# BATT_INPUT.net
KiCad netlist of a schematic drawn in EAGLE
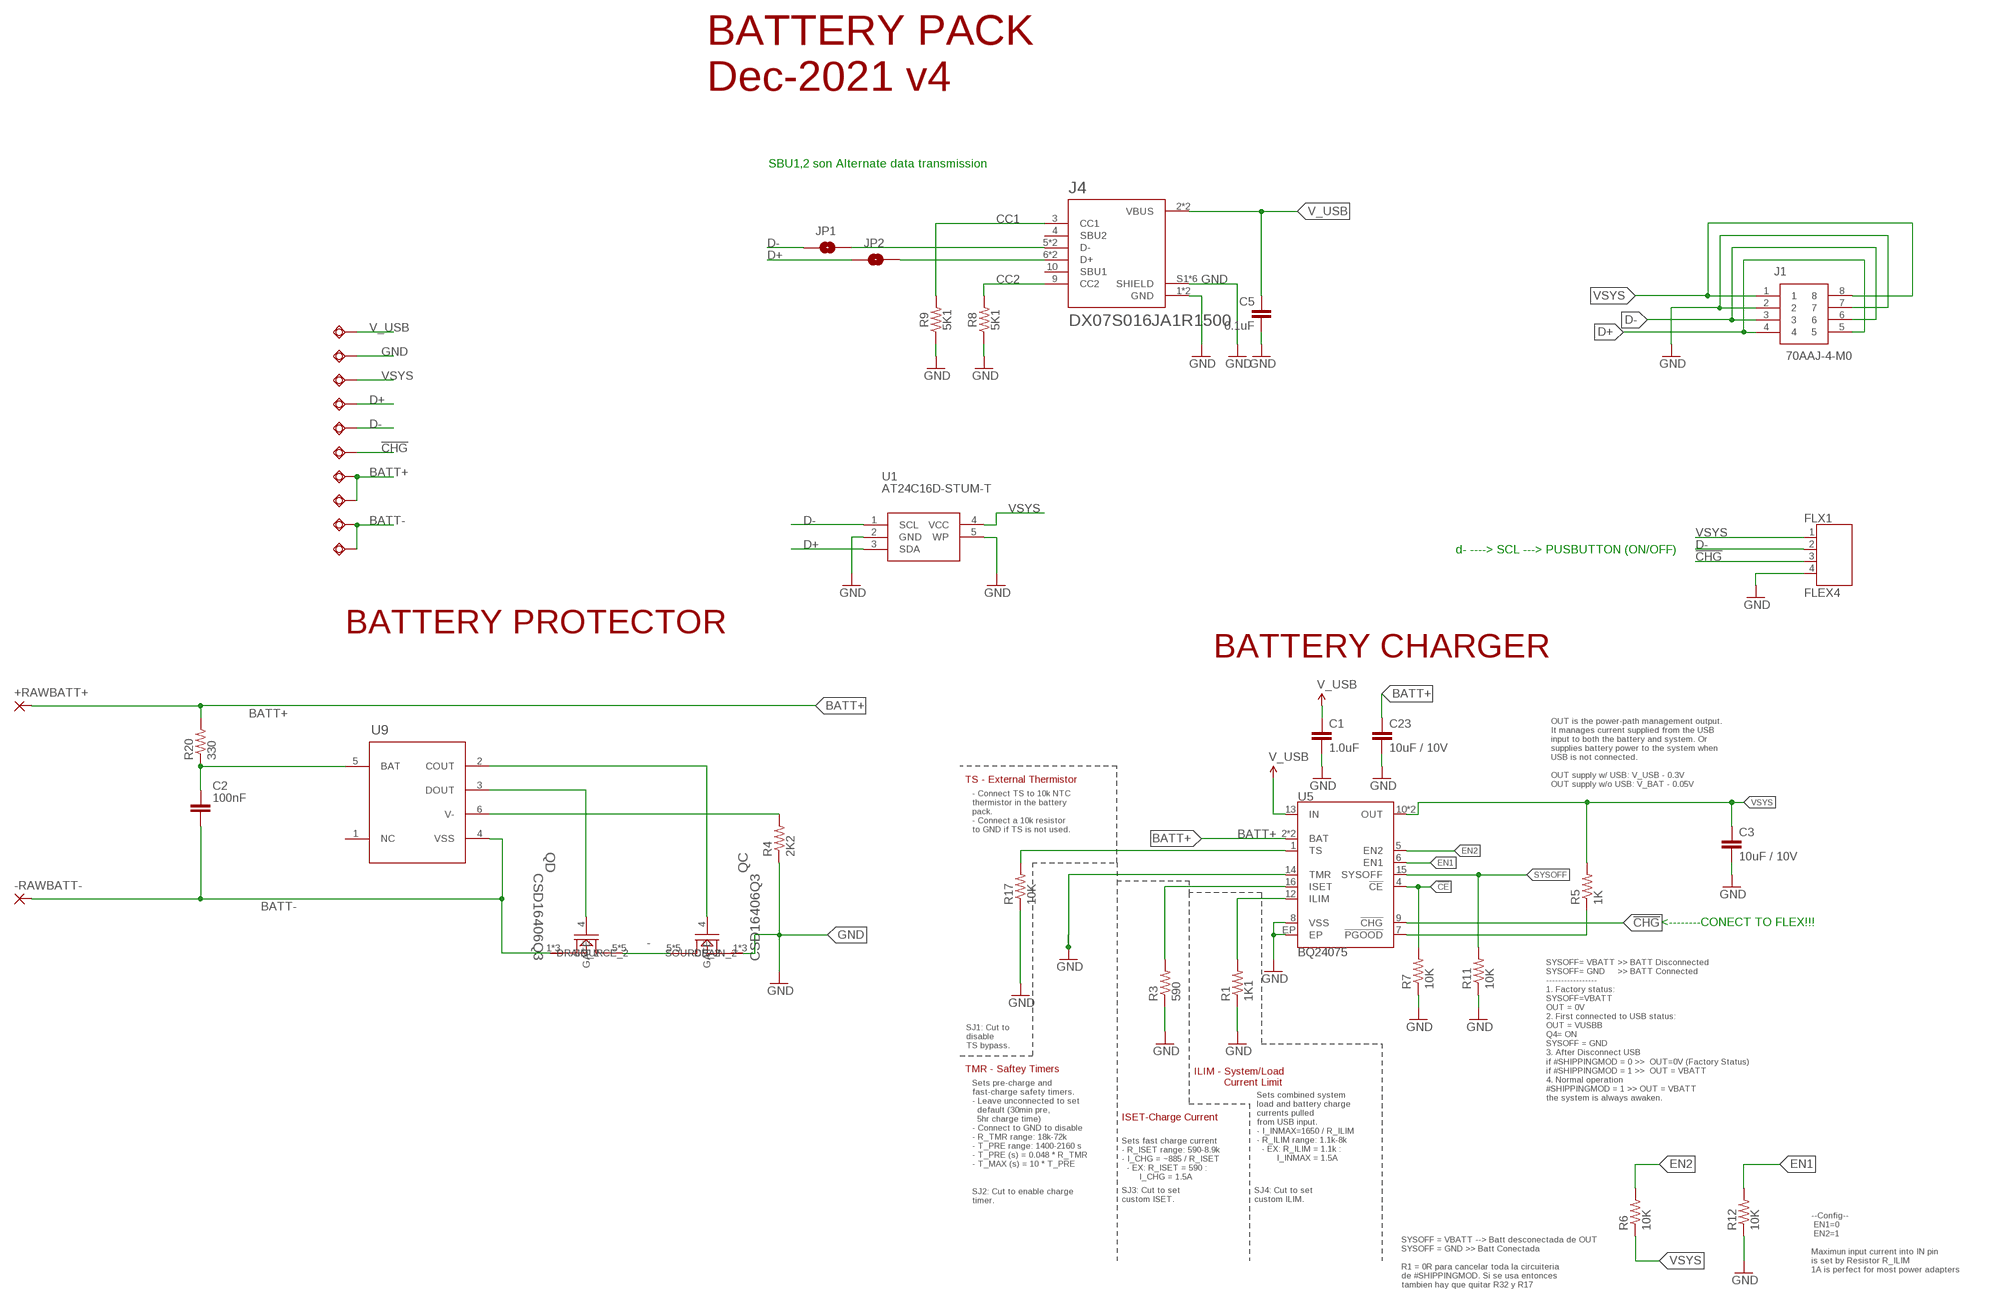
[diagram p0: schematic, sheet 1]

(export (version "E")
  (design (tool "Eeschema 10.0.6"))
  (components
    (comp (ref "!CHG!")
      (value "TESTPAD_TPSQB1,27")
      (footprint "eagle-import:TESTPAD_B1,27")
      (libsource (lib "eagle-import") (part "TESTPAD_TPSQB1,27"))
    )
    (comp (ref "+RAWBATT+")
      (value "SMD5")
      (footprint "eagle-import:SMD2,54-5,08")
      (libsource (lib "eagle-import") (part "SMD5"))
    )
    (comp (ref "-RAWBATT-")
      (value "SMD5")
      (footprint "eagle-import:SMD2,54-5,08")
      (libsource (lib "eagle-import") (part "SMD5"))
    )
    (comp (ref "BATT+1")
      (value "TESTPAD_TPSQB1,27")
      (footprint "eagle-import:TESTPAD_B1,27")
      (libsource (lib "eagle-import") (part "TESTPAD_TPSQB1,27"))
    )
    (comp (ref "BATT+2")
      (value "TESTPAD_TPSQB1,27")
      (footprint "eagle-import:TESTPAD_B1,27")
      (libsource (lib "eagle-import") (part "TESTPAD_TPSQB1,27"))
    )
    (comp (ref "BATT-1")
      (value "TESTPAD_TPSQB1,27")
      (footprint "eagle-import:TESTPAD_B1,27")
      (libsource (lib "eagle-import") (part "TESTPAD_TPSQB1,27"))
    )
    (comp (ref "BATT-2")
      (value "TESTPAD_TPSQB1,27")
      (footprint "eagle-import:TESTPAD_B1,27")
      (libsource (lib "eagle-import") (part "TESTPAD_TPSQB1,27"))
    )
    (comp (ref "C1")
      (value "1.0uF")
      (footprint "eagle-import:0603")
      (libsource (lib "eagle-import") (part "1.0UF-0603-16V-10%"))
    )
    (comp (ref "C2")
      (value "100nF")
      (footprint "eagle-import:CAPC1608X85")
      (libsource (lib "eagle-import") (part "CCHIP-0603(1608-METRIC)_"))
    )
    (comp (ref "C3")
      (value "10uF / 10V")
      (footprint "eagle-import:0805-CAP")
      (libsource (lib "eagle-import") (part "10UF10V10%(0805)"))
    )
    (comp (ref "C5")
      (value "0.1uF")
      (footprint "eagle-import:0603")
      (libsource (lib "eagle-import") (part "0.1UF-0603-25V-(+80/-20%)"))
    )
    (comp (ref "C23")
      (value "10uF / 10V")
      (footprint "eagle-import:0805-CAP")
      (libsource (lib "eagle-import") (part "10UF10V10%(0805)"))
    )
    (comp (ref "D+")
      (value "TESTPAD_TPSQB1,27")
      (footprint "eagle-import:TESTPAD_B1,27")
      (libsource (lib "eagle-import") (part "TESTPAD_TPSQB1,27"))
    )
    (comp (ref "D-")
      (value "TESTPAD_TPSQB1,27")
      (footprint "eagle-import:TESTPAD_B1,27")
      (libsource (lib "eagle-import") (part "TESTPAD_TPSQB1,27"))
    )
    (comp (ref "FLX1")
      (value "FLEX4")
      (footprint "eagle-import:FLEX4")
      (libsource (lib "eagle-import") (part "FLEX4"))
    )
    (comp (ref "GND")
      (value "TESTPAD_TPSQB1,27")
      (footprint "eagle-import:TESTPAD_B1,27")
      (libsource (lib "eagle-import") (part "TESTPAD_TPSQB1,27"))
    )
    (comp (ref "J1")
      (value "70AAJ-4-M0")
      (footprint "eagle-import:70AAJ4M0")
      (fields (field (name "MOUSER_PART_NUMBER") "652-70AAJ-4-M0"))
      (libsource (lib "eagle-import") (part "70AAJ-4-M0"))
    )
    (comp (ref "J4")
      (value "DX07S016JA1R1500")
      (footprint "eagle-import:JAE_DX07S016JA1R1500")
      (fields
        (field (name "DIGI-KEY_PART_NUMBER") "670-DX07S016JA1R1500CT-ND")
        (field (name "MF") "JAE Electronics")
      )
      (libsource (lib "eagle-import") (part "DX07S016JA1R1500"))
    )
    (comp (ref "JP1")
      (value "JUMPER-SMT_2_NO_SILK")
      (footprint "eagle-import:SMT-JUMPER_2_NO_SILK")
      (libsource (lib "eagle-import") (part "JUMPER-SMT_2_NO_SILK"))
    )
    (comp (ref "JP2")
      (value "JUMPER-SMT_2_NO_SILK")
      (footprint "eagle-import:SMT-JUMPER_2_NO_SILK")
      (libsource (lib "eagle-import") (part "JUMPER-SMT_2_NO_SILK"))
    )
    (comp (ref "QC")
      (value "CSD16406Q3")
      (footprint "eagle-import:DQG0008A")
      (libsource (lib "eagle-import") (part "CSD16406Q3"))
    )
    (comp (ref "QD")
      (value "CSD16406Q3")
      (footprint "eagle-import:DQG0008A")
      (libsource (lib "eagle-import") (part "CSD16406Q3"))
    )
    (comp (ref "R1")
      (value "1K1")
      (footprint "eagle-import:0402")
      (libsource (lib "eagle-import") (part "RESISTOR0402"))
    )
    (comp (ref "R3")
      (value "590")
      (footprint "eagle-import:0402")
      (libsource (lib "eagle-import") (part "RESISTOR0402"))
    )
    (comp (ref "R4")
      (value "2K2")
      (footprint "eagle-import:0402")
      (libsource (lib "eagle-import") (part "RESISTOR0402"))
    )
    (comp (ref "R5")
      (value "1K")
      (footprint "eagle-import:0402")
      (libsource (lib "eagle-import") (part "RESISTOR0402"))
    )
    (comp (ref "R6")
      (value "10K")
      (footprint "eagle-import:0402")
      (libsource (lib "eagle-import") (part "RESISTOR0402"))
    )
    (comp (ref "R7")
      (value "10K")
      (footprint "eagle-import:0402")
      (libsource (lib "eagle-import") (part "RESISTOR0402"))
    )
    (comp (ref "R8")
      (value "5K1")
      (footprint "eagle-import:0402")
      (libsource (lib "eagle-import") (part "RESISTOR0402"))
    )
    (comp (ref "R9")
      (value "5K1")
      (footprint "eagle-import:0402")
      (libsource (lib "eagle-import") (part "RESISTOR0402"))
    )
    (comp (ref "R11")
      (value "10K")
      (footprint "eagle-import:0402")
      (libsource (lib "eagle-import") (part "RESISTOR0402"))
    )
    (comp (ref "R12")
      (value "10K")
      (footprint "eagle-import:0402")
      (libsource (lib "eagle-import") (part "RESISTOR0402"))
    )
    (comp (ref "R17")
      (value "10K")
      (footprint "eagle-import:0402")
      (libsource (lib "eagle-import") (part "RESISTOR0402"))
    )
    (comp (ref "R20")
      (value "330")
      (footprint "eagle-import:0402")
      (libsource (lib "eagle-import") (part "RESISTOR0402"))
    )
    (comp (ref "U1")
      (value "AT24C16D-STUM-T")
      (footprint "eagle-import:SOT95P280X100-5N")
      (fields (field (name "MOUSER_PART_NUMBER") "556-AT24C16D-STUM-T"))
      (libsource (lib "eagle-import") (part "AT24C16D-STUM-T"))
    )
    (comp (ref "U5")
      (value "BQ24075")
      (footprint "eagle-import:PVQFN-N16")
      (libsource (lib "eagle-import") (part "BQ24075"))
    )
    (comp (ref "U9")
      (value "Value")
      (footprint "eagle-import:DSE0006A")
      (fields (field (name "MANUFACTURER") "Texas Instruments") (field (name "PARTNUMBER") "BQ29705DSER"))
      (libsource (lib "eagle-import") (part "BQ29700DSER"))
    )
    (comp (ref "VSYS")
      (value "TESTPAD_TPSQB1,27")
      (footprint "eagle-import:TESTPAD_B1,27")
      (libsource (lib "eagle-import") (part "TESTPAD_TPSQB1,27"))
    )
    (comp (ref "V_USB")
      (value "TESTPAD_TPSQB1,27")
      (footprint "eagle-import:TESTPAD_B1,27")
      (libsource (lib "eagle-import") (part "TESTPAD_TPSQB1,27"))
    )
  )
  (nets
    (net (code "1") (name "/-") (class "Default")
      (node (ref "QC") (pin "5") (pinfunction "DRAIN_2_5") (pintype "passive"))
      (node (ref "QC") (pin "6") (pinfunction "DRAIN_2_6") (pintype "passive"))
      (node (ref "QC") (pin "7") (pinfunction "DRAIN_2_7") (pintype "passive"))
      (node (ref "QC") (pin "8") (pinfunction "DRAIN_2_8") (pintype "passive"))
      (node (ref "QC") (pin "9") (pinfunction "DRAIN_2_9") (pintype "passive"))
      (node (ref "QD") (pin "5") (pinfunction "DRAIN_2_5") (pintype "passive"))
      (node (ref "QD") (pin "6") (pinfunction "DRAIN_2_6") (pintype "passive"))
      (node (ref "QD") (pin "7") (pinfunction "DRAIN_2_7") (pintype "passive"))
      (node (ref "QD") (pin "8") (pinfunction "DRAIN_2_8") (pintype "passive"))
      (node (ref "QD") (pin "9") (pinfunction "DRAIN_2_9") (pintype "passive"))
    )
    (net (code "2") (name "/BATT-") (class "Default")
      (node (ref "-RAWBATT-") (pin "1") (pinfunction "P_1") (pintype "passive"))
      (node (ref "BATT-1") (pin "TP") (pinfunction "TP_TP") (pintype "input"))
      (node (ref "BATT-2") (pin "TP") (pinfunction "TP_TP") (pintype "input"))
      (node (ref "C2") (pin "2") (pinfunction "2_2") (pintype "passive"))
      (node (ref "QD") (pin "1") (pinfunction "SOURCE_2_1") (pintype "passive"))
      (node (ref "QD") (pin "2") (pinfunction "SOURCE_2_2") (pintype "passive"))
      (node (ref "QD") (pin "3") (pinfunction "SOURCE_2_3") (pintype "passive"))
      (node (ref "U9") (pin "4") (pinfunction "VSS_4") (pintype "power_in"))
    )
    (net (code "3") (name "/CC1") (class "Default")
      (node (ref "J4") (pin "3") (pinfunction "CC1_3") (pintype "passive"))
      (node (ref "R9") (pin "2") (pinfunction "2_2") (pintype "passive"))
    )
    (net (code "4") (name "/CC2") (class "Default")
      (node (ref "J4") (pin "9") (pinfunction "CC2_9") (pintype "passive"))
      (node (ref "R8") (pin "2") (pinfunction "2_2") (pintype "passive"))
    )
    (net (code "5") (name "/~{CE}") (class "Default")
      (node (ref "R7") (pin "2") (pinfunction "2_2") (pintype "passive"))
      (node (ref "U5") (pin "4") (pinfunction "~{CE}_4") (pintype "bidirectional"))
    )
    (net (code "6") (name "/~{CHG}") (class "Default")
      (node (ref "!CHG!") (pin "TP") (pinfunction "TP_TP") (pintype "input"))
      (node (ref "FLX1") (pin "3") (pinfunction "3_3") (pintype "passive"))
      (node (ref "U5") (pin "9") (pinfunction "~{CHG}_9") (pintype "bidirectional"))
    )
    (net (code "7") (name "BATT+") (class "Default")
      (node (ref "+RAWBATT+") (pin "1") (pinfunction "P_1") (pintype "passive"))
      (node (ref "BATT+1") (pin "TP") (pinfunction "TP_TP") (pintype "input"))
      (node (ref "BATT+2") (pin "TP") (pinfunction "TP_TP") (pintype "input"))
      (node (ref "C23") (pin "1") (pinfunction "1_1") (pintype "passive"))
      (node (ref "R20") (pin "2") (pinfunction "2_2") (pintype "passive"))
      (node (ref "U5") (pin "2") (pinfunction "BAT_2") (pintype "bidirectional"))
      (node (ref "U5") (pin "3") (pinfunction "BAT_3") (pintype "bidirectional"))
    )
    (net (code "8") (name "D+") (class "Default")
      (node (ref "D+") (pin "TP") (pinfunction "TP_TP") (pintype "input"))
      (node (ref "J1") (pin "4") (pinfunction "4_4") (pintype "bidirectional"))
      (node (ref "J1") (pin "5") (pinfunction "5_5") (pintype "bidirectional"))
      (node (ref "JP2") (pin "1") (pinfunction "1_1") (pintype "passive"))
      (node (ref "U1") (pin "3") (pinfunction "SDA_3") (pintype "bidirectional"))
    )
    (net (code "9") (name "D-") (class "Default")
      (node (ref "D-") (pin "TP") (pinfunction "TP_TP") (pintype "input"))
      (node (ref "FLX1") (pin "2") (pinfunction "2_2") (pintype "passive"))
      (node (ref "J1") (pin "3") (pinfunction "3_3") (pintype "bidirectional"))
      (node (ref "J1") (pin "6") (pinfunction "6_6") (pintype "bidirectional"))
      (node (ref "JP1") (pin "1") (pinfunction "1_1") (pintype "passive"))
      (node (ref "U1") (pin "1") (pinfunction "SCL_1") (pintype "bidirectional"))
    )
    (net (code "10") (name "EN1") (class "Default")
      (node (ref "R12") (pin "2") (pinfunction "2_2") (pintype "passive"))
      (node (ref "U5") (pin "6") (pinfunction "EN1_6") (pintype "bidirectional"))
    )
    (net (code "11") (name "EN2") (class "Default")
      (node (ref "R6") (pin "2") (pinfunction "2_2") (pintype "passive"))
      (node (ref "U5") (pin "5") (pinfunction "EN2_5") (pintype "bidirectional"))
    )
    (net (code "12") (name "GND") (class "Default")
      (node (ref "C1") (pin "2") (pinfunction "2_2") (pintype "passive"))
      (node (ref "C23") (pin "2") (pinfunction "2_2") (pintype "passive"))
      (node (ref "C3") (pin "2") (pinfunction "2_2") (pintype "passive"))
      (node (ref "C5") (pin "2") (pinfunction "2_2") (pintype "passive"))
      (node (ref "FLX1") (pin "4") (pinfunction "4_4") (pintype "passive"))
      (node (ref "GND") (pin "TP") (pinfunction "TP_TP") (pintype "input"))
      (node (ref "J1") (pin "2") (pinfunction "2_2") (pintype "bidirectional"))
      (node (ref "J1") (pin "7") (pinfunction "7_7") (pintype "bidirectional"))
      (node (ref "J4") (pin "1") (pinfunction "GND_1") (pintype "power_in"))
      (node (ref "J4") (pin "12") (pinfunction "GND_12") (pintype "power_in"))
      (node (ref "J4") (pin "S1") (pinfunction "SHIELD_S1") (pintype "passive"))
      (node (ref "J4") (pin "S2") (pinfunction "SHIELD_S2") (pintype "passive"))
      (node (ref "J4") (pin "S3") (pinfunction "SHIELD_S3") (pintype "passive"))
      (node (ref "J4") (pin "S4") (pinfunction "SHIELD_S4") (pintype "passive"))
      (node (ref "J4") (pin "S5") (pinfunction "SHIELD_S5") (pintype "passive"))
      (node (ref "J4") (pin "S6") (pinfunction "SHIELD_S6") (pintype "passive"))
      (node (ref "QC") (pin "1") (pinfunction "SOURCE_2_1") (pintype "passive"))
      (node (ref "QC") (pin "2") (pinfunction "SOURCE_2_2") (pintype "passive"))
      (node (ref "QC") (pin "3") (pinfunction "SOURCE_2_3") (pintype "passive"))
      (node (ref "R1") (pin "1") (pinfunction "1_1") (pintype "passive"))
      (node (ref "R11") (pin "1") (pinfunction "1_1") (pintype "passive"))
      (node (ref "R12") (pin "1") (pinfunction "1_1") (pintype "passive"))
      (node (ref "R17") (pin "1") (pinfunction "1_1") (pintype "passive"))
      (node (ref "R3") (pin "1") (pinfunction "1_1") (pintype "passive"))
      (node (ref "R4") (pin "1") (pinfunction "1_1") (pintype "passive"))
      (node (ref "R7") (pin "1") (pinfunction "1_1") (pintype "passive"))
      (node (ref "R8") (pin "1") (pinfunction "1_1") (pintype "passive"))
      (node (ref "R9") (pin "1") (pinfunction "1_1") (pintype "passive"))
      (node (ref "U1") (pin "2") (pinfunction "GND_2") (pintype "power_in"))
      (node (ref "U1") (pin "5") (pinfunction "WP_5") (pintype "input"))
      (node (ref "U5") (pin "14") (pinfunction "TMR_14") (pintype "bidirectional"))
      (node (ref "U5") (pin "8") (pinfunction "VSS_8") (pintype "bidirectional"))
      (node (ref "U5") (pin "EP") (pinfunction "EP_EP") (pintype "bidirectional"))
    )
    (net (code "13") (name "Net-(J4-D+-Pad6)") (class "Default")
      (node (ref "J4") (pin "6") (pinfunction "D+_6") (pintype "passive"))
      (node (ref "J4") (pin "7") (pinfunction "D+_7") (pintype "passive"))
      (node (ref "JP2") (pin "2") (pinfunction "2_2") (pintype "passive"))
    )
    (net (code "14") (name "Net-(J4-D--Pad5)") (class "Default")
      (node (ref "J4") (pin "5") (pinfunction "D-_5") (pintype "passive"))
      (node (ref "J4") (pin "8") (pinfunction "D-_8") (pintype "passive"))
      (node (ref "JP1") (pin "2") (pinfunction "2_2") (pintype "passive"))
    )
    (net (code "15") (name "Net-(QC-GATE)") (class "Default")
      (node (ref "QC") (pin "4") (pinfunction "GATE_4") (pintype "passive"))
      (node (ref "U9") (pin "2") (pinfunction "COUT_2") (pintype "output"))
    )
    (net (code "16") (name "Net-(QD-GATE)") (class "Default")
      (node (ref "QD") (pin "4") (pinfunction "GATE_4") (pintype "passive"))
      (node (ref "U9") (pin "3") (pinfunction "DOUT_3") (pintype "output"))
    )
    (net (code "17") (name "Net-(U5-ILIM)") (class "Default")
      (node (ref "R1") (pin "2") (pinfunction "2_2") (pintype "passive"))
      (node (ref "U5") (pin "12") (pinfunction "ILIM_12") (pintype "bidirectional"))
    )
    (net (code "18") (name "Net-(U5-ISET)") (class "Default")
      (node (ref "R3") (pin "2") (pinfunction "2_2") (pintype "passive"))
      (node (ref "U5") (pin "16") (pinfunction "ISET_16") (pintype "bidirectional"))
    )
    (net (code "19") (name "Net-(U5-TS)") (class "Default")
      (node (ref "R17") (pin "2") (pinfunction "2_2") (pintype "passive"))
      (node (ref "U5") (pin "1") (pinfunction "TS_1") (pintype "bidirectional"))
    )
    (net (code "20") (name "Net-(U5-~{PGOOD})") (class "Default")
      (node (ref "R5") (pin "1") (pinfunction "1_1") (pintype "passive"))
      (node (ref "U5") (pin "7") (pinfunction "~{PGOOD}_7") (pintype "bidirectional"))
    )
    (net (code "21") (name "Net-(U9-BAT)") (class "Default")
      (node (ref "C2") (pin "1") (pinfunction "1_1") (pintype "passive"))
      (node (ref "R20") (pin "1") (pinfunction "1_1") (pintype "passive"))
      (node (ref "U9") (pin "5") (pinfunction "BAT_5") (pintype "power_in"))
    )
    (net (code "22") (name "Net-(U9-V-)") (class "Default")
      (node (ref "R4") (pin "2") (pinfunction "2_2") (pintype "passive"))
      (node (ref "U9") (pin "6") (pinfunction "V-_6") (pintype "bidirectional"))
    )
    (net (code "23") (name "SYSOFF") (class "Default")
      (node (ref "R11") (pin "2") (pinfunction "2_2") (pintype "passive"))
      (node (ref "U5") (pin "15") (pinfunction "SYSOFF_15") (pintype "bidirectional"))
    )
    (net (code "24") (name "VSYS") (class "Default")
      (node (ref "C3") (pin "1") (pinfunction "1_1") (pintype "passive"))
      (node (ref "FLX1") (pin "1") (pinfunction "1_1") (pintype "passive"))
      (node (ref "J1") (pin "1") (pinfunction "1_1") (pintype "bidirectional"))
      (node (ref "J1") (pin "8") (pinfunction "8_8") (pintype "bidirectional"))
      (node (ref "R5") (pin "2") (pinfunction "2_2") (pintype "passive"))
      (node (ref "R6") (pin "1") (pinfunction "1_1") (pintype "passive"))
      (node (ref "U1") (pin "4") (pinfunction "VCC_4") (pintype "power_in"))
      (node (ref "U5") (pin "10") (pinfunction "OUT_10") (pintype "bidirectional"))
      (node (ref "U5") (pin "11") (pinfunction "OUT_11") (pintype "bidirectional"))
      (node (ref "VSYS") (pin "TP") (pinfunction "TP_TP") (pintype "input"))
    )
    (net (code "25") (name "V_USB") (class "Default")
      (node (ref "C1") (pin "1") (pinfunction "1_1") (pintype "passive"))
      (node (ref "C5") (pin "1") (pinfunction "1_1") (pintype "passive"))
      (node (ref "J4") (pin "11") (pinfunction "VBUS_11") (pintype "power_in"))
      (node (ref "J4") (pin "2") (pinfunction "VBUS_2") (pintype "power_in"))
      (node (ref "U5") (pin "13") (pinfunction "IN_13") (pintype "bidirectional"))
      (node (ref "V_USB") (pin "TP") (pinfunction "TP_TP") (pintype "input"))
    )
    (net (code "26") (name "unconnected-(J4-SBU1-Pad10)") (class "Default")
      (node (ref "J4") (pin "10") (pinfunction "SBU1_10") (pintype "passive"))
    )
    (net (code "27") (name "unconnected-(J4-SBU2-Pad4)") (class "Default")
      (node (ref "J4") (pin "4") (pinfunction "SBU2_4") (pintype "passive"))
    )
    (net (code "28") (name "unconnected-(U9-NC-Pad1)") (class "Default")
      (node (ref "U9") (pin "1") (pinfunction "NC_1") (pintype "passive"))
    )
  )
)
